# MCU.net
KiCad netlist of a schematic drawn in Altium Designer
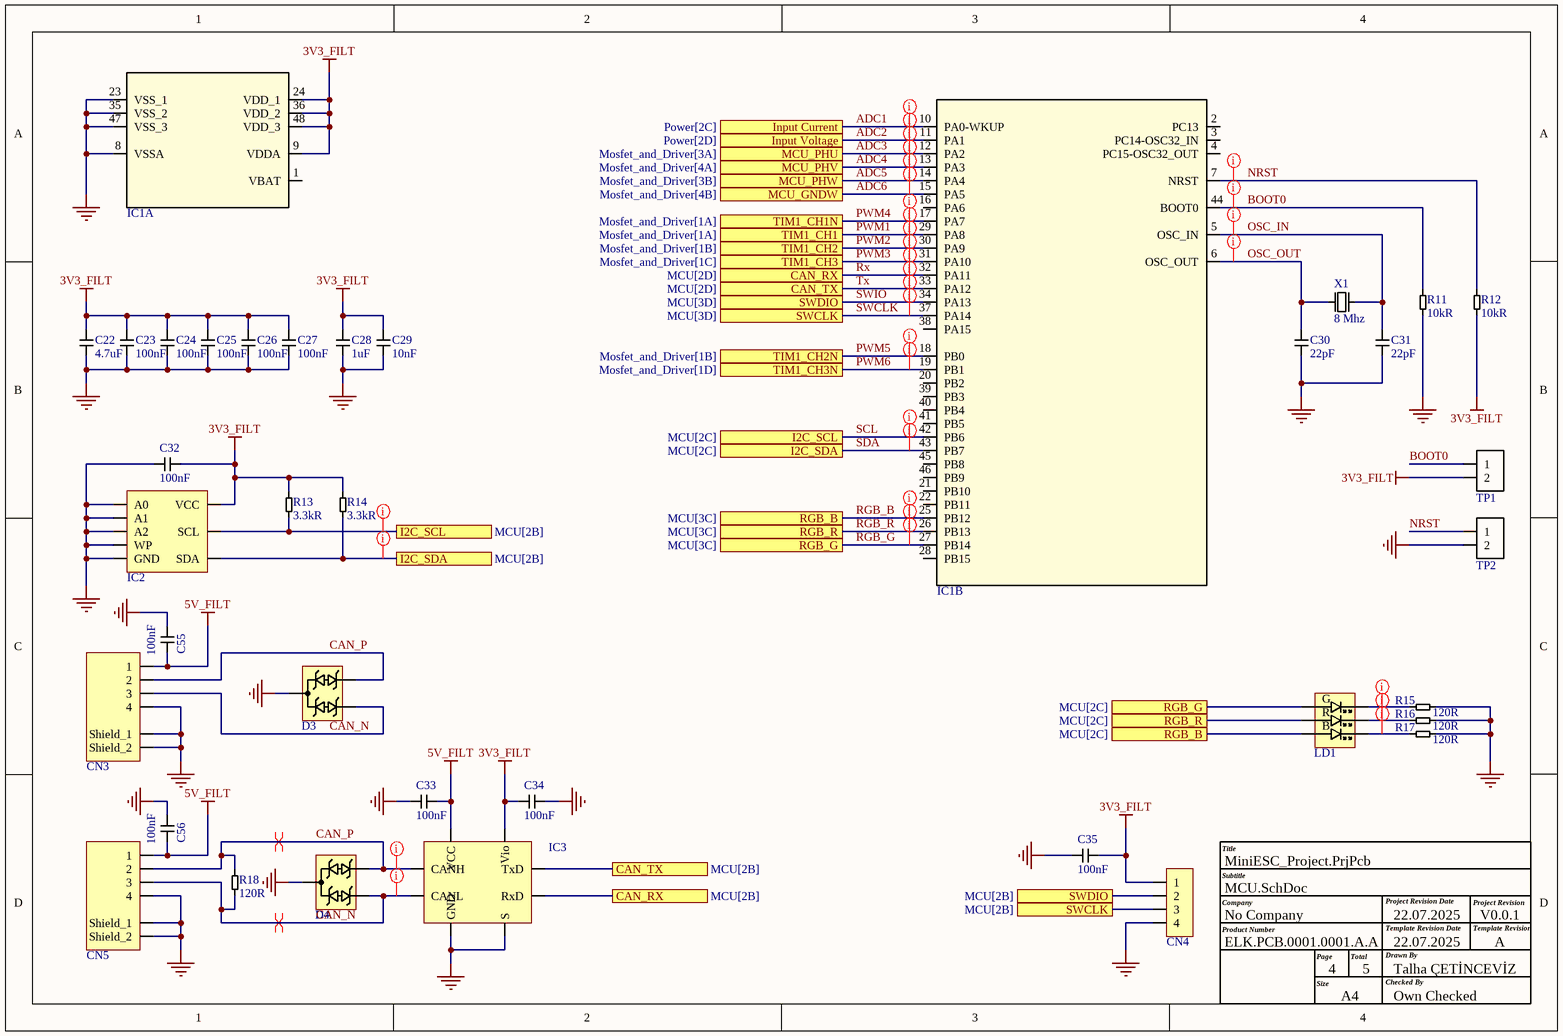
[diagram p0: MCU.SchDoc]

(export (version "E")
  (design (tool "Eeschema 10.0.6"))
  (components
    (comp (ref "C22")
      (value "4.7uF")
      (footprint "CAP 0603")
      (description "16V 4.7uF X5R ±10% 0603 Multilayer Ceramic Capacitors MLCC - SMD/SMT ROHS")
      (fields
        (field (name "MANUFACTURER") "Samsung")
        (field (name "MANUFACTURER PART NUMBER") "CL10A475KO8NNNC")
      )
      (libsource (lib "ESC_Int") (part "CL10A475KO8NNNC"))
    )
    (comp (ref "C23")
      (value "100nF")
      (footprint "CAP 0603")
      (description "Multilayer Ceramic Capacitor, CC Series, 0.1 - F, - 10%, X7R, 50 V, 0603 [1608 Metric]")
      (fields
        (field (name "MANUFACTURER") "Yageo")
        (field (name "MANUFACTURER PART NUMBER") "CC0603KRX7R9BB104")
      )
      (libsource (lib "ESC_Int") (part "CC0603KRX7R9BB104"))
    )
    (comp (ref "C24")
      (value "100nF")
      (footprint "CAP 0603")
      (description "Multilayer Ceramic Capacitor, CC Series, 0.1 - F, - 10%, X7R, 50 V, 0603 [1608 Metric]")
      (fields
        (field (name "MANUFACTURER") "Yageo")
        (field (name "MANUFACTURER PART NUMBER") "CC0603KRX7R9BB104")
      )
      (libsource (lib "ESC_Int") (part "CC0603KRX7R9BB104"))
    )
    (comp (ref "C25")
      (value "100nF")
      (footprint "CAP 0603")
      (description "Multilayer Ceramic Capacitor, CC Series, 0.1 - F, - 10%, X7R, 50 V, 0603 [1608 Metric]")
      (fields
        (field (name "MANUFACTURER") "Yageo")
        (field (name "MANUFACTURER PART NUMBER") "CC0603KRX7R9BB104")
      )
      (libsource (lib "ESC_Int") (part "CC0603KRX7R9BB104"))
    )
    (comp (ref "C26")
      (value "100nF")
      (footprint "CAP 0603")
      (description "Multilayer Ceramic Capacitor, CC Series, 0.1 - F, - 10%, X7R, 50 V, 0603 [1608 Metric]")
      (fields
        (field (name "MANUFACTURER") "Yageo")
        (field (name "MANUFACTURER PART NUMBER") "CC0603KRX7R9BB104")
      )
      (libsource (lib "ESC_Int") (part "CC0603KRX7R9BB104"))
    )
    (comp (ref "C27")
      (value "100nF")
      (footprint "CAP 0603")
      (description "Multilayer Ceramic Capacitor, CC Series, 0.1 - F, - 10%, X7R, 50 V, 0603 [1608 Metric]")
      (fields
        (field (name "MANUFACTURER") "Yageo")
        (field (name "MANUFACTURER PART NUMBER") "CC0603KRX7R9BB104")
      )
      (libsource (lib "ESC_Int") (part "CC0603KRX7R9BB104"))
    )
    (comp (ref "C28")
      (value "1uF")
      (footprint "CAP 0603")
      (description "16V 1uF X7R ±10% 0603 Multilayer Ceramic Capacitors MLCC - SMD/SMT ROHS")
      (fields
        (field (name "MANUFACTURER") "Samsung")
        (field (name "MANUFACTURER PART NUMBER") "CL10B105KO8NNNC")
      )
      (libsource (lib "ESC_Int") (part "CL10B105KO8NNNC"))
    )
    (comp (ref "C29")
      (value "10nF")
      (footprint "CAP 0603")
      (description "50V 10nF X7R ±10% 0603 Multilayer Ceramic Capacitors MLCC - SMD/SMT ROHS")
      (fields
        (field (name "MANUFACTURER") "Samsung")
        (field (name "MANUFACTURER PART NUMBER") "CL10B103KB8NNNC")
      )
      (libsource (lib "ESC_Int") (part "CL10B103KB8NNNC"))
    )
    (comp (ref "C30")
      (value "22pF")
      (footprint "CAP 0603")
      (description "MLCC (1608) 0603 22pF 50VDC ±5% C0G (NP0)")
      (fields
        (field (name "MANUFACTURER") "VIKING")
        (field (name "MANUFACTURER PART NUMBER") "MCF03JTN500220")
      )
      (libsource (lib "ESC_Int") (part "MCF03JTN500220"))
    )
    (comp (ref "C31")
      (value "22pF")
      (footprint "CAP 0603")
      (description "MLCC (1608) 0603 22pF 50VDC ±5% C0G (NP0)")
      (fields
        (field (name "MANUFACTURER") "VIKING")
        (field (name "MANUFACTURER PART NUMBER") "MCF03JTN500220")
      )
      (libsource (lib "ESC_Int") (part "MCF03JTN500220"))
    )
    (comp (ref "C32")
      (value "100nF")
      (footprint "CAP 0603")
      (description "Multilayer Ceramic Capacitor, CC Series, 0.1 - F, - 10%, X7R, 50 V, 0603 [1608 Metric]")
      (fields
        (field (name "MANUFACTURER") "Yageo")
        (field (name "MANUFACTURER PART NUMBER") "CC0603KRX7R9BB104")
      )
      (libsource (lib "ESC_Int") (part "CC0603KRX7R9BB104"))
    )
    (comp (ref "C33")
      (value "100nF")
      (footprint "CAP 0603")
      (description "Multilayer Ceramic Capacitor, CC Series, 0.1 - F, - 10%, X7R, 50 V, 0603 [1608 Metric]")
      (fields
        (field (name "MANUFACTURER") "Yageo")
        (field (name "MANUFACTURER PART NUMBER") "CC0603KRX7R9BB104")
      )
      (libsource (lib "ESC_Int") (part "CC0603KRX7R9BB104"))
    )
    (comp (ref "C34")
      (value "100nF")
      (footprint "CAP 0603")
      (description "Multilayer Ceramic Capacitor, CC Series, 0.1 - F, - 10%, X7R, 50 V, 0603 [1608 Metric]")
      (fields
        (field (name "MANUFACTURER") "Yageo")
        (field (name "MANUFACTURER PART NUMBER") "CC0603KRX7R9BB104")
      )
      (libsource (lib "ESC_Int") (part "CC0603KRX7R9BB104"))
    )
    (comp (ref "C35")
      (value "100nF")
      (footprint "CAP 0603")
      (description "Multilayer Ceramic Capacitor, CC Series, 0.1 - F, - 10%, X7R, 50 V, 0603 [1608 Metric]")
      (fields
        (field (name "MANUFACTURER") "Yageo")
        (field (name "MANUFACTURER PART NUMBER") "CC0603KRX7R9BB104")
      )
      (libsource (lib "ESC_Int") (part "CC0603KRX7R9BB104"))
    )
    (comp (ref "C55")
      (value "100nF")
      (footprint "CAP 0603")
      (description "Multilayer Ceramic Capacitor, CC Series, 0.1 - F, - 10%, X7R, 50 V, 0603 [1608 Metric]")
      (fields
        (field (name "MANUFACTURER") "Yageo")
        (field (name "MANUFACTURER PART NUMBER") "CC0603KRX7R9BB104")
      )
      (libsource (lib "ESC_Int") (part "CC0603KRX7R9BB104"))
    )
    (comp (ref "C56")
      (value "100nF")
      (footprint "CAP 0603")
      (description "Multilayer Ceramic Capacitor, CC Series, 0.1 - F, - 10%, X7R, 50 V, 0603 [1608 Metric]")
      (fields
        (field (name "MANUFACTURER") "Yageo")
        (field (name "MANUFACTURER PART NUMBER") "CC0603KRX7R9BB104")
      )
      (libsource (lib "ESC_Int") (part "CC0603KRX7R9BB104"))
    )
    (comp (ref "CN3")
      (value "5024940470")
      (footprint "5024940470")
      (description "2.00mm Pitch CLIK-Mate Wire-to-Board PCB Receptacle, Single Row, Right-Angle, 4 Circuits")
      (fields (field (name "MANUFACTURER") "Molex"))
      (libsource (lib "ESC_Int") (part "5024940470"))
    )
    (comp (ref "CN4")
      (value "4 Pin SMD")
      (footprint "4Pin SMD")
      (libsource (lib "ESC_Int") (part "4 Pin SMD"))
    )
    (comp (ref "CN5")
      (value "5024940470")
      (footprint "5024940470")
      (description "2.00mm Pitch CLIK-Mate Wire-to-Board PCB Receptacle, Single Row, Right-Angle, 4 Circuits")
      (fields (field (name "MANUFACTURER") "Molex"))
      (libsource (lib "ESC_Int") (part "5024940470"))
    )
    (comp (ref "D3")
      (value "PESD1CAN-HT")
      (footprint "SOT23-3")
      (description "DIODE TVS 200W 24V SOT23")
      (fields
        (field (name "MANUFACTURER") "Nexperia")
        (field (name "MANUFACTURER PART NUMBER") "PESD1CAN-UX")
      )
      (libsource (lib "ESC_Int") (part "PESD1CAN-HT"))
    )
    (comp (ref "D4")
      (value "PESD1CAN-HT")
      (footprint "SOT23-3")
      (description "DIODE TVS 200W 24V SOT23")
      (fields
        (field (name "MANUFACTURER") "Nexperia")
        (field (name "MANUFACTURER PART NUMBER") "PESD1CAN-UX")
      )
      (libsource (lib "ESC_Int") (part "PESD1CAN-HT"))
    )
    (comp (ref "IC1")
      (value "STM32F103CBT7TR")
      (footprint "LQFP-48")
      (description "RISC Microcontroller, 32-Bit, FLASH, CORTEX-M3 CPU, 1.25MHz, CMOS, PQFP48")
      (fields (field (name "MANUFACTURER") "STMicroelectronics"))
      (libsource (lib "ESC_Int") (part "STM32F103CBT7TR"))
    )
    (comp (ref "IC2")
      (value "AT24C128C-SSHM-T")
      (footprint "SOIC-8")
      (description "AT24C128C-SSHM-T, ATMEL, EEPROM Serial-2Wire 128K-bit 16K x 8 2.5V/3.3V/5V8-Pin SOIC")
      (fields (field (name "MANUFACTURER") "Microchip"))
      (libsource (lib "ESC_Int") (part "AT24C128C-SSHM-T"))
    )
    (comp (ref "IC3")
      (value "TJA1051T/3,118")
      (footprint "SOIC-8")
      (description "TJA1051 Series 3 V 1 Mbit/s Surface Mount High-Speed CAN Transceiver - SOIC-8")
      (fields (field (name "MANUFACTURER") "NXP Semiconductors"))
      (libsource (lib "ESC_Int") (part "TJA1051T/3,118"))
    )
    (comp (ref "LD1")
      (value "HLAF5060H248BS36FU76GCS1")
      (footprint "LED 5050")
      (description "LED SMD 5050 RGB R:250mcd G:1300mcd B:350mcd@20mA")
      (fields
        (field (name "MANUFACTURER") "Honglitronic")
        (field (name "MANUFACTURER PART NUMBER") "HL-AF-5060H248BS36FU76GC-S1-THL")
      )
      (libsource (lib "ESC_Int") (part "HLAF5060H248BS36FU76GCS1"))
    )
    (comp (ref "R11")
      (value "10kR")
      (footprint "RES 0603")
      (description "SMD Chip Resistor, 10 Kohm, ½ 1%, 100 Mw, 0603 [1608 Metric], Thick Film, General Purpose")
      (fields
        (field (name "MANUFACTURER") "Yageo")
        (field (name "MANUFACTURER PART NUMBER") "RC0603FR-0710KL")
      )
      (libsource (lib "ESC_Int") (part "RC0603FR-0710KL"))
    )
    (comp (ref "R12")
      (value "10kR")
      (footprint "RES 0603")
      (description "SMD Chip Resistor, 10 Kohm, ½ 1%, 100 Mw, 0603 [1608 Metric], Thick Film, General Purpose")
      (fields
        (field (name "MANUFACTURER") "Yageo")
        (field (name "MANUFACTURER PART NUMBER") "RC0603FR-0710KL")
      )
      (libsource (lib "ESC_Int") (part "RC0603FR-0710KL"))
    )
    (comp (ref "R13")
      (value "3.3kR")
      (footprint "RES 0603")
      (description "Res Thick Film 0603 3.3K Ohm 1% 0.1W(1/10W) ±100ppm/°C Pad SMD T/R")
      (fields
        (field (name "MANUFACTURER") "Multicomp")
        (field (name "MANUFACTURER PART NUMBER") "MC0603SAF3301T5E")
      )
      (libsource (lib "ESC_Int") (part "0603SAF3301T5E"))
    )
    (comp (ref "R14")
      (value "3.3kR")
      (footprint "RES 0603")
      (description "Res Thick Film 0603 3.3K Ohm 1% 0.1W(1/10W) ±100ppm/°C Pad SMD T/R")
      (fields
        (field (name "MANUFACTURER") "Multicomp")
        (field (name "MANUFACTURER PART NUMBER") "MC0603SAF3301T5E")
      )
      (libsource (lib "ESC_Int") (part "0603SAF3301T5E"))
    )
    (comp (ref "R15")
      (value "120R")
      (footprint "RES 0603")
      (description "RES.(1608) 0603 120 Ohms 1% 1/10W-S 100PPM")
      (fields
        (field (name "MANUFACTURER") "ROYALOHM")
        (field (name "MANUFACTURER PART NUMBER") "0603SAF1200T5E")
      )
      (libsource (lib "ESC_Int") (part "0603SAF1200T5E"))
    )
    (comp (ref "R16")
      (value "120R")
      (footprint "RES 0603")
      (description "RES.(1608) 0603 120 Ohms 1% 1/10W-S 100PPM")
      (fields
        (field (name "MANUFACTURER") "ROYALOHM")
        (field (name "MANUFACTURER PART NUMBER") "0603SAF1200T5E")
      )
      (libsource (lib "ESC_Int") (part "0603SAF1200T5E"))
    )
    (comp (ref "R17")
      (value "120R")
      (footprint "RES 0603")
      (description "RES.(1608) 0603 120 Ohms 1% 1/10W-S 100PPM")
      (fields
        (field (name "MANUFACTURER") "ROYALOHM")
        (field (name "MANUFACTURER PART NUMBER") "0603SAF1200T5E")
      )
      (libsource (lib "ESC_Int") (part "0603SAF1200T5E"))
    )
    (comp (ref "R18")
      (value "120R")
      (footprint "RES 0603")
      (description "RES.(1608) 0603 120 Ohms 1% 1/10W-S 100PPM")
      (fields
        (field (name "MANUFACTURER") "ROYALOHM")
        (field (name "MANUFACTURER PART NUMBER") "0603SAF1200T5E")
      )
      (libsource (lib "ESC_Int") (part "0603SAF1200T5E"))
    )
    (comp (ref "TP1") (value "TP_Mini") (footprint "TP") (libsource (lib "ESC_Int") (part "TP_Mini")))
    (comp (ref "TP2") (value "TP_Mini") (footprint "TP") (libsource (lib "ESC_Int") (part "TP_Mini")))
    (comp (ref "X1")
      (value "8 Mhz")
      (footprint "HC-49/US")
      (description "CRYSTAL 8MHz HC49SMT 16pF SMD TR RALTRON")
      (fields
        (field (name "MANUFACTURER") "Raltron Electronics")
        (field (name "MANUFACTURER PART NUMBER") "AS-8.000-16-SMD-TR")
      )
      (libsource (lib "ESC_Int") (part "AS-8.000-16-SMD-TR"))
    )
  )
  (nets
    (net (code "1") (name "/ADC1") (class "Default")
      (node (ref "IC1") (pin "10") (pinfunction "PA0-WKUP_10") (pintype "passive"))
    )
    (net (code "2") (name "/ADC2") (class "Default")
      (node (ref "IC1") (pin "11") (pinfunction "PA1_11") (pintype "passive"))
    )
    (net (code "3") (name "/ADC3") (class "Default")
      (node (ref "IC1") (pin "12") (pinfunction "PA2_12") (pintype "passive"))
    )
    (net (code "4") (name "/ADC4") (class "Default")
      (node (ref "IC1") (pin "13") (pinfunction "PA3_13") (pintype "passive"))
    )
    (net (code "5") (name "/ADC5") (class "Default")
      (node (ref "IC1") (pin "14") (pinfunction "PA4_14") (pintype "passive"))
    )
    (net (code "6") (name "/ADC6") (class "Default")
      (node (ref "IC1") (pin "15") (pinfunction "PA5_15") (pintype "passive"))
    )
    (net (code "7") (name "/BOOT0") (class "Default")
      (node (ref "IC1") (pin "44") (pinfunction "BOOT0_44") (pintype "passive"))
      (node (ref "R11") (pin "2") (pinfunction "2_2") (pintype "passive"))
      (node (ref "TP1") (pin "1") (pinfunction "1_1") (pintype "passive"))
    )
    (net (code "8") (name "/CAN_N") (class "Default")
      (node (ref "CN3") (pin "3") (pinfunction "3_3") (pintype "passive"))
      (node (ref "CN5") (pin "3") (pinfunction "3_3") (pintype "passive"))
      (node (ref "D3") (pin "2") (pinfunction "2_2") (pintype "passive"))
      (node (ref "D4") (pin "2") (pinfunction "2_2") (pintype "passive"))
      (node (ref "IC3") (pin "6") (pinfunction "CANL_6") (pintype "passive"))
      (node (ref "R18") (pin "1") (pinfunction "1_1") (pintype "passive"))
    )
    (net (code "9") (name "/CAN_P") (class "Default")
      (node (ref "CN3") (pin "2") (pinfunction "2_2") (pintype "passive"))
      (node (ref "CN5") (pin "2") (pinfunction "2_2") (pintype "passive"))
      (node (ref "D3") (pin "1") (pinfunction "1_1") (pintype "passive"))
      (node (ref "D4") (pin "1") (pinfunction "1_1") (pintype "passive"))
      (node (ref "IC3") (pin "7") (pinfunction "CANH_7") (pintype "passive"))
      (node (ref "R18") (pin "2") (pinfunction "2_2") (pintype "passive"))
    )
    (net (code "10") (name "/NRST") (class "Default")
      (node (ref "IC1") (pin "7") (pinfunction "NRST_7") (pintype "passive"))
      (node (ref "R12") (pin "2") (pinfunction "2_2") (pintype "passive"))
      (node (ref "TP2") (pin "1") (pinfunction "1_1") (pintype "passive"))
    )
    (net (code "11") (name "/OSC_IN") (class "Default")
      (node (ref "C31") (pin "2") (pinfunction "2_2") (pintype "passive"))
      (node (ref "IC1") (pin "5") (pinfunction "OSC_IN_5") (pintype "passive"))
      (node (ref "X1") (pin "2") (pinfunction "2_2") (pintype "passive"))
    )
    (net (code "12") (name "/OSC_OUT") (class "Default")
      (node (ref "C30") (pin "2") (pinfunction "2_2") (pintype "passive"))
      (node (ref "IC1") (pin "6") (pinfunction "OSC_OUT_6") (pintype "passive"))
      (node (ref "X1") (pin "1") (pinfunction "1_1") (pintype "passive"))
    )
    (net (code "13") (name "/PWM1") (class "Default")
      (node (ref "IC1") (pin "29") (pinfunction "PA8_29") (pintype "passive"))
    )
    (net (code "14") (name "/PWM2") (class "Default")
      (node (ref "IC1") (pin "30") (pinfunction "PA9_30") (pintype "passive"))
    )
    (net (code "15") (name "/PWM3") (class "Default")
      (node (ref "IC1") (pin "31") (pinfunction "PA10_31") (pintype "passive"))
    )
    (net (code "16") (name "/PWM4") (class "Default")
      (node (ref "IC1") (pin "17") (pinfunction "PA7_17") (pintype "passive"))
    )
    (net (code "17") (name "/PWM5") (class "Default")
      (node (ref "IC1") (pin "18") (pinfunction "PB0_18") (pintype "passive"))
    )
    (net (code "18") (name "/PWM6") (class "Default")
      (node (ref "IC1") (pin "19") (pinfunction "PB1_19") (pintype "passive"))
    )
    (net (code "19") (name "/RGB_B") (class "Default")
      (node (ref "IC1") (pin "25") (pinfunction "PB12_25") (pintype "passive"))
      (node (ref "LD1") (pin "3") (pinfunction "Blue_Anode_3") (pintype "passive"))
    )
    (net (code "20") (name "/RGB_G") (class "Default")
      (node (ref "IC1") (pin "27") (pinfunction "PB14_27") (pintype "passive"))
      (node (ref "LD1") (pin "1") (pinfunction "Green_Anode_1") (pintype "passive"))
    )
    (net (code "21") (name "/RGB_R") (class "Default")
      (node (ref "IC1") (pin "26") (pinfunction "PB13_26") (pintype "passive"))
      (node (ref "LD1") (pin "2") (pinfunction "Red_Anode_2") (pintype "passive"))
    )
    (net (code "22") (name "/Rx") (class "Default")
      (node (ref "IC1") (pin "32") (pinfunction "PA11_32") (pintype "passive"))
      (node (ref "IC3") (pin "4") (pinfunction "RxD_4") (pintype "passive"))
    )
    (net (code "23") (name "/SCL") (class "Default")
      (node (ref "IC1") (pin "42") (pinfunction "PB6_42") (pintype "passive"))
      (node (ref "IC2") (pin "6") (pinfunction "SCL_6") (pintype "passive"))
      (node (ref "R13") (pin "1") (pinfunction "1_1") (pintype "passive"))
    )
    (net (code "24") (name "/SDA") (class "Default")
      (node (ref "IC1") (pin "43") (pinfunction "PB7_43") (pintype "passive"))
      (node (ref "IC2") (pin "5") (pinfunction "SDA_5") (pintype "passive"))
      (node (ref "R14") (pin "1") (pinfunction "1_1") (pintype "passive"))
    )
    (net (code "25") (name "/SWCLK") (class "Default")
      (node (ref "CN4") (pin "3") (pinfunction "3_3") (pintype "passive"))
      (node (ref "IC1") (pin "37") (pinfunction "PA14_37") (pintype "passive"))
    )
    (net (code "26") (name "/SWIO") (class "Default")
      (node (ref "CN4") (pin "2") (pinfunction "2_2") (pintype "passive"))
      (node (ref "IC1") (pin "34") (pinfunction "PA13_34") (pintype "passive"))
    )
    (net (code "27") (name "/Tx") (class "Default")
      (node (ref "IC1") (pin "33") (pinfunction "PA12_33") (pintype "passive"))
      (node (ref "IC3") (pin "1") (pinfunction "TxD_1") (pintype "passive"))
    )
    (net (code "28") (name "3V3_FILT") (class "Default")
      (node (ref "C22") (pin "2") (pinfunction "2_2") (pintype "passive"))
      (node (ref "C23") (pin "2") (pinfunction "2_2") (pintype "passive"))
      (node (ref "C24") (pin "2") (pinfunction "2_2") (pintype "passive"))
      (node (ref "C25") (pin "2") (pinfunction "2_2") (pintype "passive"))
      (node (ref "C26") (pin "2") (pinfunction "2_2") (pintype "passive"))
      (node (ref "C27") (pin "2") (pinfunction "2_2") (pintype "passive"))
      (node (ref "C28") (pin "2") (pinfunction "2_2") (pintype "passive"))
      (node (ref "C29") (pin "2") (pinfunction "2_2") (pintype "passive"))
      (node (ref "C32") (pin "1") (pinfunction "1_1") (pintype "passive"))
      (node (ref "C34") (pin "2") (pinfunction "2_2") (pintype "passive"))
      (node (ref "C35") (pin "1") (pinfunction "1_1") (pintype "passive"))
      (node (ref "CN4") (pin "1") (pinfunction "1_1") (pintype "passive"))
      (node (ref "IC1") (pin "24") (pinfunction "VDD_1_24") (pintype "power_in"))
      (node (ref "IC1") (pin "36") (pinfunction "VDD_2_36") (pintype "power_in"))
      (node (ref "IC1") (pin "48") (pinfunction "VDD_3_48") (pintype "power_in"))
      (node (ref "IC1") (pin "9") (pinfunction "VDDA_9") (pintype "power_in"))
      (node (ref "IC2") (pin "8") (pinfunction "VCC_8") (pintype "passive"))
      (node (ref "IC3") (pin "5") (pinfunction "Vio_5") (pintype "passive"))
      (node (ref "R12") (pin "1") (pinfunction "1_1") (pintype "passive"))
      (node (ref "R13") (pin "2") (pinfunction "2_2") (pintype "passive"))
      (node (ref "R14") (pin "2") (pinfunction "2_2") (pintype "passive"))
      (node (ref "TP1") (pin "2") (pinfunction "2_2") (pintype "passive"))
    )
    (net (code "29") (name "5V_FILT") (class "Default")
      (node (ref "C33") (pin "1") (pinfunction "1_1") (pintype "passive"))
      (node (ref "C55") (pin "2") (pinfunction "2_2") (pintype "passive"))
      (node (ref "C56") (pin "2") (pinfunction "2_2") (pintype "passive"))
      (node (ref "CN3") (pin "1") (pinfunction "1_1") (pintype "passive"))
      (node (ref "CN5") (pin "1") (pinfunction "1_1") (pintype "passive"))
      (node (ref "IC3") (pin "3") (pinfunction "VCC_3") (pintype "passive"))
    )
    (net (code "30") (name "GND") (class "Default")
      (node (ref "C22") (pin "1") (pinfunction "1_1") (pintype "passive"))
      (node (ref "C23") (pin "1") (pinfunction "1_1") (pintype "passive"))
      (node (ref "C24") (pin "1") (pinfunction "1_1") (pintype "passive"))
      (node (ref "C25") (pin "1") (pinfunction "1_1") (pintype "passive"))
      (node (ref "C26") (pin "1") (pinfunction "1_1") (pintype "passive"))
      (node (ref "C27") (pin "1") (pinfunction "1_1") (pintype "passive"))
      (node (ref "C28") (pin "1") (pinfunction "1_1") (pintype "passive"))
      (node (ref "C29") (pin "1") (pinfunction "1_1") (pintype "passive"))
      (node (ref "C30") (pin "1") (pinfunction "3_1") (pintype "passive"))
      (node (ref "C31") (pin "1") (pinfunction "3_1") (pintype "passive"))
      (node (ref "C32") (pin "2") (pinfunction "2_2") (pintype "passive"))
      (node (ref "C33") (pin "2") (pinfunction "2_2") (pintype "passive"))
      (node (ref "C34") (pin "1") (pinfunction "1_1") (pintype "passive"))
      (node (ref "C35") (pin "2") (pinfunction "2_2") (pintype "passive"))
      (node (ref "C55") (pin "1") (pinfunction "1_1") (pintype "passive"))
      (node (ref "C56") (pin "1") (pinfunction "1_1") (pintype "passive"))
      (node (ref "CN3") (pin "4") (pinfunction "4_4") (pintype "passive"))
      (node (ref "CN3") (pin "5") (pinfunction "Shield_1_5") (pintype "passive"))
      (node (ref "CN3") (pin "6") (pinfunction "Shield_2_6") (pintype "passive"))
      (node (ref "CN4") (pin "4") (pinfunction "4_4") (pintype "passive"))
      (node (ref "CN5") (pin "4") (pinfunction "4_4") (pintype "passive"))
      (node (ref "CN5") (pin "5") (pinfunction "Shield_1_5") (pintype "passive"))
      (node (ref "CN5") (pin "6") (pinfunction "Shield_2_6") (pintype "passive"))
      (node (ref "D3") (pin "3") (pinfunction "3_3") (pintype "passive"))
      (node (ref "D4") (pin "3") (pinfunction "3_3") (pintype "passive"))
      (node (ref "IC1") (pin "23") (pinfunction "VSS_1_23") (pintype "power_in"))
      (node (ref "IC1") (pin "35") (pinfunction "VSS_2_35") (pintype "power_in"))
      (node (ref "IC1") (pin "47") (pinfunction "VSS_3_47") (pintype "power_in"))
      (node (ref "IC1") (pin "8") (pinfunction "VSSA_8") (pintype "power_in"))
      (node (ref "IC2") (pin "1") (pinfunction "A0_1") (pintype "passive"))
      (node (ref "IC2") (pin "2") (pinfunction "A1_2") (pintype "passive"))
      (node (ref "IC2") (pin "3") (pinfunction "A2_3") (pintype "passive"))
      (node (ref "IC2") (pin "4") (pinfunction "GND_4") (pintype "passive"))
      (node (ref "IC2") (pin "7") (pinfunction "WP_7") (pintype "passive"))
      (node (ref "IC3") (pin "2") (pinfunction "GND_2") (pintype "passive"))
      (node (ref "IC3") (pin "8") (pinfunction "S_8") (pintype "passive"))
      (node (ref "R11") (pin "1") (pinfunction "1_1") (pintype "passive"))
      (node (ref "R15") (pin "2") (pinfunction "2_2") (pintype "passive"))
      (node (ref "R16") (pin "2") (pinfunction "2_2") (pintype "passive"))
      (node (ref "R17") (pin "2") (pinfunction "2_2") (pintype "passive"))
      (node (ref "TP2") (pin "2") (pinfunction "2_2") (pintype "passive"))
    )
    (net (code "31") (name "Net-(LD1-Blue_Cathode)") (class "Default")
      (node (ref "LD1") (pin "4") (pinfunction "Blue_Cathode_4") (pintype "passive"))
      (node (ref "R17") (pin "1") (pinfunction "1_1") (pintype "passive"))
    )
    (net (code "32") (name "Net-(LD1-Green_Cathode)") (class "Default")
      (node (ref "LD1") (pin "6") (pinfunction "Green_Cathode_6") (pintype "passive"))
      (node (ref "R15") (pin "1") (pinfunction "1_1") (pintype "passive"))
    )
    (net (code "33") (name "Net-(LD1-Red_Cathode)") (class "Default")
      (node (ref "LD1") (pin "5") (pinfunction "Red_Cathode_5") (pintype "passive"))
      (node (ref "R16") (pin "1") (pinfunction "1_1") (pintype "passive"))
    )
    (net (code "34") (name "unconnected-(IC1A-VBAT-Pad1)") (class "Default")
      (node (ref "IC1") (pin "1") (pinfunction "VBAT_1") (pintype "power_in"))
    )
    (net (code "35") (name "unconnected-(IC1B-PA6-Pad16)") (class "Default")
      (node (ref "IC1") (pin "16") (pinfunction "PA6_16") (pintype "passive"))
    )
    (net (code "36") (name "unconnected-(IC1B-PA15-Pad38)") (class "Default")
      (node (ref "IC1") (pin "38") (pinfunction "PA15_38") (pintype "passive"))
    )
    (net (code "37") (name "unconnected-(IC1B-PB2-Pad20)") (class "Default")
      (node (ref "IC1") (pin "20") (pinfunction "PB2_20") (pintype "passive"))
    )
    (net (code "38") (name "unconnected-(IC1B-PB3-Pad39)") (class "Default")
      (node (ref "IC1") (pin "39") (pinfunction "PB3_39") (pintype "passive"))
    )
    (net (code "39") (name "unconnected-(IC1B-PB4-Pad40)") (class "Default")
      (node (ref "IC1") (pin "40") (pinfunction "PB4_40") (pintype "passive"))
    )
    (net (code "40") (name "unconnected-(IC1B-PB5-Pad41)") (class "Default")
      (node (ref "IC1") (pin "41") (pinfunction "PB5_41") (pintype "passive"))
    )
    (net (code "41") (name "unconnected-(IC1B-PB8-Pad45)") (class "Default")
      (node (ref "IC1") (pin "45") (pinfunction "PB8_45") (pintype "passive"))
    )
    (net (code "42") (name "unconnected-(IC1B-PB9-Pad46)") (class "Default")
      (node (ref "IC1") (pin "46") (pinfunction "PB9_46") (pintype "passive"))
    )
    (net (code "43") (name "unconnected-(IC1B-PB10-Pad21)") (class "Default")
      (node (ref "IC1") (pin "21") (pinfunction "PB10_21") (pintype "passive"))
    )
    (net (code "44") (name "unconnected-(IC1B-PB11-Pad22)") (class "Default")
      (node (ref "IC1") (pin "22") (pinfunction "PB11_22") (pintype "passive"))
    )
    (net (code "45") (name "unconnected-(IC1B-PB15-Pad28)") (class "Default")
      (node (ref "IC1") (pin "28") (pinfunction "PB15_28") (pintype "passive"))
    )
    (net (code "46") (name "unconnected-(IC1B-PC13-Pad2)") (class "Default")
      (node (ref "IC1") (pin "2") (pinfunction "PC13_2") (pintype "passive"))
    )
    (net (code "47") (name "unconnected-(IC1B-PC14-OSC32_IN-Pad3)") (class "Default")
      (node (ref "IC1") (pin "3") (pinfunction "PC14-OSC32_IN_3") (pintype "passive"))
    )
    (net (code "48") (name "unconnected-(IC1B-PC15-OSC32_OUT-Pad4)") (class "Default")
      (node (ref "IC1") (pin "4") (pinfunction "PC15-OSC32_OUT_4") (pintype "passive"))
    )
  )
)
